# PLWD_MCU_IO.net
KiCad netlist of a schematic drawn in Altium Designer
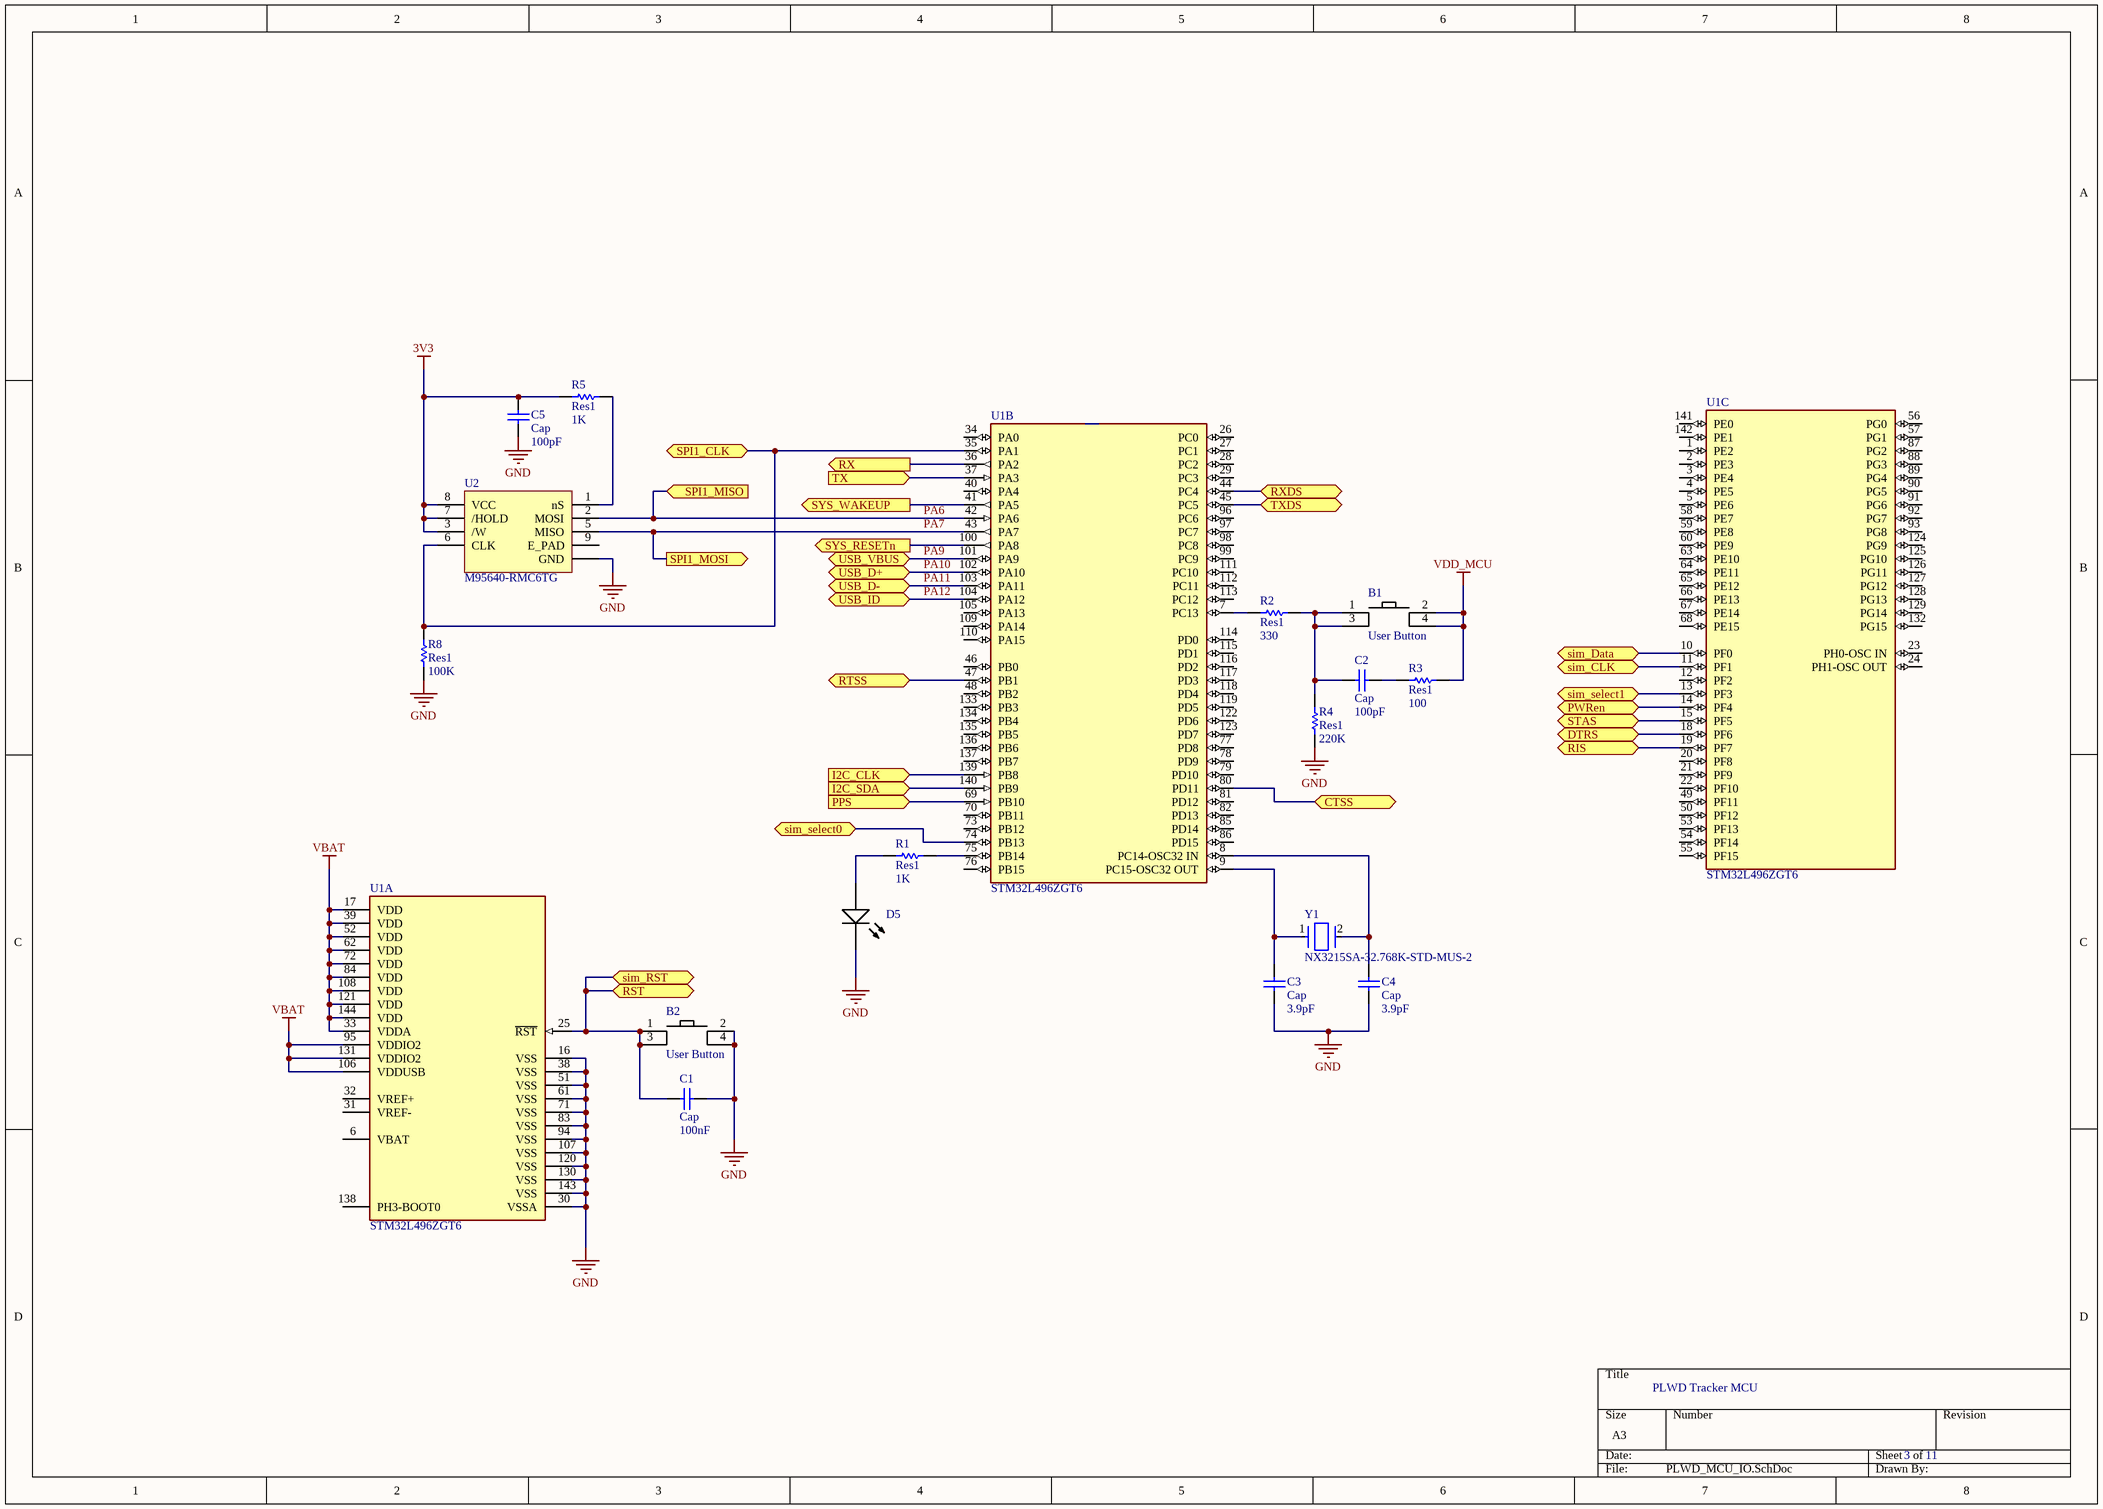
[diagram p0: PLWD_MCU_IO.SchDoc]

(export (version "E")
  (design (tool "Eeschema 10.0.6"))
  (components
    (comp (ref "B1") (value "User Button") (libsource (lib "PLWD_PartLib") (part "button")))
    (comp (ref "B2") (value "User Button") (libsource (lib "PLWD_PartLib") (part "button")))
    (comp (ref "C1")
      (value "Cap")
      (footprint "RAD-0.3")
      (description "Capacitor")
      (fields (field (name "ALTIUM_VALUE") "100nF") (field (name "PUBLISHER") "Altium Limited"))
      (libsource (lib "Miscellaneous Devices") (part "Cap"))
    )
    (comp (ref "C2")
      (value "Cap")
      (footprint "RAD-0.3")
      (description "Capacitor")
      (fields (field (name "ALTIUM_VALUE") "100pF") (field (name "PUBLISHER") "Altium Limited"))
      (libsource (lib "Miscellaneous Devices") (part "Cap"))
    )
    (comp (ref "C3")
      (value "Cap")
      (footprint "RAD-0.3")
      (description "Capacitor")
      (fields (field (name "ALTIUM_VALUE") "3.9pF") (field (name "PUBLISHER") "Altium Limited"))
      (libsource (lib "Miscellaneous Devices") (part "Cap"))
    )
    (comp (ref "C4")
      (value "Cap")
      (footprint "RAD-0.3")
      (description "Capacitor")
      (fields (field (name "ALTIUM_VALUE") "3.9pF") (field (name "PUBLISHER") "Altium Limited"))
      (libsource (lib "Miscellaneous Devices") (part "Cap"))
    )
    (comp (ref "C5")
      (value "Cap")
      (footprint "RAD-0.3")
      (description "Capacitor")
      (fields (field (name "ALTIUM_VALUE") "100pF") (field (name "PUBLISHER") "Altium Limited"))
      (libsource (lib "Miscellaneous Devices") (part "Cap"))
    )
    (comp (ref "D5")
      (value "16-219A/T2D-AR2T1QY/3T")
      (footprint "EVRL-0402-2_V")
      (description "Chip LED, White, 5 V, 10 mA, 30 mW, -40 to 85 degC, 2-Pin SMD (0402), RoHS, Tape and Reel")
      (fields (field (name "POWER") "30mW") (field (name "MANUFACTURER") "Everlight Electronics"))
      (libsource (lib "Carleton University") (part "LED-WHITE-AK-2"))
    )
    (comp (ref "R1")
      (value "Res1")
      (footprint "AXIAL-0.3")
      (description "Resistor")
      (fields (field (name "ALTIUM_VALUE") "1K") (field (name "PUBLISHER") "Altium Limited"))
      (libsource (lib "Miscellaneous Devices") (part "Res1"))
    )
    (comp (ref "R2")
      (value "Res1")
      (footprint "AXIAL-0.3")
      (description "Resistor")
      (fields (field (name "ALTIUM_VALUE") "330") (field (name "PUBLISHER") "Altium Limited"))
      (libsource (lib "Miscellaneous Devices") (part "Res1"))
    )
    (comp (ref "R3")
      (value "Res1")
      (footprint "AXIAL-0.3")
      (description "Resistor")
      (fields (field (name "ALTIUM_VALUE") "100") (field (name "PUBLISHER") "Altium Limited"))
      (libsource (lib "Miscellaneous Devices") (part "Res1"))
    )
    (comp (ref "R4")
      (value "Res1")
      (footprint "AXIAL-0.3")
      (description "Resistor")
      (fields (field (name "ALTIUM_VALUE") "220K") (field (name "PUBLISHER") "Altium Limited"))
      (libsource (lib "Miscellaneous Devices") (part "Res1"))
    )
    (comp (ref "R5")
      (value "Res1")
      (footprint "AXIAL-0.3")
      (description "Resistor")
      (fields (field (name "ALTIUM_VALUE") "1K") (field (name "PUBLISHER") "Altium Limited"))
      (libsource (lib "Miscellaneous Devices") (part "Res1"))
    )
    (comp (ref "R8")
      (value "Res1")
      (footprint "AXIAL-0.3")
      (description "Resistor")
      (fields (field (name "ALTIUM_VALUE") "100K") (field (name "PUBLISHER") "Altium Limited"))
      (libsource (lib "Miscellaneous Devices") (part "Res1"))
    )
    (comp (ref "U1")
      (value "STM32L496ZGT6")
      (footprint "FP-LQFP144-1A-MFG")
      (description "IC MCU 32BIT 1MB FLASH 144LQFP")
      (fields
        (field (name "MANUFACTURER") "STMicroelectronics")
        (field (name "OCTOPART") "https://octopart.com/stm32l496zgt6-stmicroelectronics-80927210")
      )
      (libsource (lib "") (part "f6bd984deb1ec052b3cf6fb0542fb75_2"))
    )
    (comp (ref "U2")
      (value "M95640-RMC6TG")
      (description "M95640 Series 64 Kb (8K x 8) 5.5 V 20 MHz SMT Serial SPI bus EEPROM - UFDFPN-8")
      (fields (field (name "MANUFACTURER") "STMicroelectronics"))
      (libsource (lib "PLWD_PartLib") (part "M95640-RMC6TG"))
    )
    (comp (ref "Y1")
      (value "NX3215SA-32.768K-STD-MUS-2")
      (footprint "FP-NX3215SA-MFG")
      (description "CRYSTAL 32.7680KHZ 12.5PF SMD")
      (libsource (lib "Altium Content Vault") (part "c23a69dc6c9e2f18f2079038eb95dd1"))
    )
  )
  (nets
    (net (code "1") (name "/CTSS") (class "Default")
      (node (ref "U1") (pin "80") (pinfunction "PD11_80") (pintype "bidirectional"))
    )
    (net (code "2") (name "/DTRS") (class "Default")
      (node (ref "U1") (pin "18") (pinfunction "PF6_18") (pintype "bidirectional"))
    )
    (net (code "3") (name "/I2C_CLK") (class "Default")
      (node (ref "U1") (pin "139") (pinfunction "PB8_139") (pintype "input"))
    )
    (net (code "4") (name "/I2C_SDA") (class "Default")
      (node (ref "U1") (pin "140") (pinfunction "PB9_140") (pintype "input"))
    )
    (net (code "5") (name "/PA6") (class "Default")
      (node (ref "U1") (pin "42") (pinfunction "PA6_42") (pintype "input"))
      (node (ref "U2") (pin "2") (pinfunction "MOSI_2") (pintype "passive"))
    )
    (net (code "6") (name "/PA7") (class "Default")
      (node (ref "U1") (pin "43") (pinfunction "PA7_43") (pintype "output"))
      (node (ref "U2") (pin "5") (pinfunction "MISO_5") (pintype "passive"))
    )
    (net (code "7") (name "/PA9") (class "Default")
      (node (ref "U1") (pin "101") (pinfunction "PA9_101") (pintype "bidirectional"))
    )
    (net (code "8") (name "/PA10") (class "Default")
      (node (ref "U1") (pin "102") (pinfunction "PA10_102") (pintype "bidirectional"))
    )
    (net (code "9") (name "/PA11") (class "Default")
      (node (ref "U1") (pin "103") (pinfunction "PA11_103") (pintype "bidirectional"))
    )
    (net (code "10") (name "/PA12") (class "Default")
      (node (ref "U1") (pin "104") (pinfunction "PA12_104") (pintype "bidirectional"))
    )
    (net (code "11") (name "/PPS") (class "Default")
      (node (ref "U1") (pin "69") (pinfunction "PB10_69") (pintype "input"))
    )
    (net (code "12") (name "/PWRen") (class "Default")
      (node (ref "U1") (pin "14") (pinfunction "PF4_14") (pintype "bidirectional"))
    )
    (net (code "13") (name "/RIS") (class "Default")
      (node (ref "U1") (pin "19") (pinfunction "PF7_19") (pintype "bidirectional"))
    )
    (net (code "14") (name "/RST") (class "Default")
      (node (ref "B2") (pin "1") (pintype "passive"))
      (node (ref "B2") (pin "3") (pintype "passive"))
      (node (ref "C1") (pin "1") (pinfunction "1_1") (pintype "passive"))
      (node (ref "U1") (pin "25") (pinfunction "~{RST}_25") (pintype "input"))
    )
    (net (code "15") (name "/RTSS") (class "Default")
      (node (ref "U1") (pin "47") (pinfunction "PB1_47") (pintype "bidirectional"))
    )
    (net (code "16") (name "/RX") (class "Default")
      (node (ref "U1") (pin "36") (pinfunction "PA2_36") (pintype "output"))
    )
    (net (code "17") (name "/RXDS") (class "Default")
      (node (ref "U1") (pin "44") (pinfunction "PC4_44") (pintype "bidirectional"))
    )
    (net (code "18") (name "/SPI1_CLK") (class "Default")
      (node (ref "R8") (pin "2") (pinfunction "2_2") (pintype "passive"))
      (node (ref "U1") (pin "35") (pinfunction "PA1_35") (pintype "bidirectional"))
      (node (ref "U2") (pin "6") (pinfunction "CLK_6") (pintype "passive"))
    )
    (net (code "19") (name "/STAS") (class "Default")
      (node (ref "U1") (pin "15") (pinfunction "PF5_15") (pintype "bidirectional"))
    )
    (net (code "20") (name "/SYS_RESETn") (class "Default")
      (node (ref "U1") (pin "100") (pinfunction "PA8_100") (pintype "output"))
    )
    (net (code "21") (name "/SYS_WAKEUP") (class "Default")
      (node (ref "U1") (pin "41") (pinfunction "PA5_41") (pintype "output"))
    )
    (net (code "22") (name "/TX") (class "Default")
      (node (ref "U1") (pin "37") (pinfunction "PA3_37") (pintype "input"))
    )
    (net (code "23") (name "/TXDS") (class "Default")
      (node (ref "U1") (pin "45") (pinfunction "PC5_45") (pintype "bidirectional"))
    )
    (net (code "24") (name "/sim_CLK") (class "Default")
      (node (ref "U1") (pin "11") (pinfunction "PF1_11") (pintype "bidirectional"))
    )
    (net (code "25") (name "/sim_Data") (class "Default")
      (node (ref "U1") (pin "10") (pinfunction "PF0_10") (pintype "bidirectional"))
    )
    (net (code "26") (name "/sim_select0") (class "Default")
      (node (ref "U1") (pin "74") (pinfunction "PB13_74") (pintype "bidirectional"))
    )
    (net (code "27") (name "/sim_select1") (class "Default")
      (node (ref "U1") (pin "13") (pinfunction "PF3_13") (pintype "bidirectional"))
    )
    (net (code "28") (name "3V3") (class "Default")
      (node (ref "C5") (pin "2") (pinfunction "2_2") (pintype "passive"))
      (node (ref "R5") (pin "1") (pinfunction "1_1") (pintype "passive"))
      (node (ref "U2") (pin "3") (pinfunction "/W_3") (pintype "passive"))
      (node (ref "U2") (pin "7") (pinfunction "/HOLD_7") (pintype "passive"))
      (node (ref "U2") (pin "8") (pinfunction "VCC_8") (pintype "passive"))
    )
    (net (code "29") (name "GND") (class "Default")
      (node (ref "B2") (pin "2") (pintype "passive"))
      (node (ref "B2") (pin "4") (pintype "passive"))
      (node (ref "C1") (pin "2") (pinfunction "2_2") (pintype "passive"))
      (node (ref "C3") (pin "1") (pinfunction "1_1") (pintype "passive"))
      (node (ref "C4") (pin "1") (pinfunction "1_1") (pintype "passive"))
      (node (ref "C5") (pin "1") (pinfunction "1_1") (pintype "passive"))
      (node (ref "D5") (pin "2") (pinfunction "K_2") (pintype "passive"))
      (node (ref "R4") (pin "1") (pinfunction "1_1") (pintype "passive"))
      (node (ref "R8") (pin "1") (pinfunction "1_1") (pintype "passive"))
      (node (ref "U1") (pin "107") (pinfunction "VSS_107") (pintype "power_in"))
      (node (ref "U1") (pin "120") (pinfunction "VSS_120") (pintype "power_in"))
      (node (ref "U1") (pin "130") (pinfunction "VSS_130") (pintype "power_in"))
      (node (ref "U1") (pin "143") (pinfunction "VSS_143") (pintype "power_in"))
      (node (ref "U1") (pin "16") (pinfunction "VSS_16") (pintype "power_in"))
      (node (ref "U1") (pin "30") (pinfunction "VSSA_30") (pintype "power_in"))
      (node (ref "U1") (pin "38") (pinfunction "VSS_38") (pintype "power_in"))
      (node (ref "U1") (pin "51") (pinfunction "VSS_51") (pintype "power_in"))
      (node (ref "U1") (pin "61") (pinfunction "VSS_61") (pintype "power_in"))
      (node (ref "U1") (pin "71") (pinfunction "VSS_71") (pintype "power_in"))
      (node (ref "U1") (pin "83") (pinfunction "VSS_83") (pintype "power_in"))
      (node (ref "U1") (pin "94") (pinfunction "VSS_94") (pintype "power_in"))
      (node (ref "U2") (pin "4") (pinfunction "GND_4") (pintype "passive"))
    )
    (net (code "30") (name "Net-(B1-Pad1)") (class "Default")
      (node (ref "B1") (pin "1") (pintype "passive"))
      (node (ref "B1") (pin "3") (pintype "passive"))
      (node (ref "C2") (pin "1") (pinfunction "1_1") (pintype "passive"))
      (node (ref "R2") (pin "2") (pinfunction "2_2") (pintype "passive"))
      (node (ref "R4") (pin "2") (pinfunction "2_2") (pintype "passive"))
    )
    (net (code "31") (name "Net-(C2-Pad2)") (class "Default")
      (node (ref "C2") (pin "2") (pinfunction "2_2") (pintype "passive"))
      (node (ref "R3") (pin "1") (pinfunction "1_1") (pintype "passive"))
    )
    (net (code "32") (name "Net-(D5-A)") (class "Default")
      (node (ref "D5") (pin "1") (pinfunction "A_1") (pintype "passive"))
      (node (ref "R1") (pin "1") (pinfunction "1_1") (pintype "passive"))
    )
    (net (code "33") (name "Net-(U1B-PB14)") (class "Default")
      (node (ref "R1") (pin "2") (pinfunction "2_2") (pintype "passive"))
      (node (ref "U1") (pin "75") (pinfunction "PB14_75") (pintype "bidirectional"))
    )
    (net (code "34") (name "Net-(U1B-PC13)") (class "Default")
      (node (ref "R2") (pin "1") (pinfunction "1_1") (pintype "passive"))
      (node (ref "U1") (pin "7") (pinfunction "PC13_7") (pintype "bidirectional"))
    )
    (net (code "35") (name "Net-(U1B-PC14-OSC32_IN)") (class "Default")
      (node (ref "C4") (pin "2") (pinfunction "2_2") (pintype "passive"))
      (node (ref "U1") (pin "8") (pinfunction "PC14-OSC32_IN_8") (pintype "bidirectional"))
      (node (ref "Y1") (pin "2") (pinfunction "2_2") (pintype "passive"))
    )
    (net (code "36") (name "Net-(U1B-PC15-OSC32_OUT)") (class "Default")
      (node (ref "C3") (pin "2") (pinfunction "2_2") (pintype "passive"))
      (node (ref "U1") (pin "9") (pinfunction "PC15-OSC32_OUT_9") (pintype "bidirectional"))
      (node (ref "Y1") (pin "1") (pinfunction "1_1") (pintype "passive"))
    )
    (net (code "37") (name "Net-(U2-nS)") (class "Default")
      (node (ref "R5") (pin "2") (pinfunction "2_2") (pintype "passive"))
      (node (ref "U2") (pin "1") (pinfunction "nS_1") (pintype "passive"))
    )
    (net (code "38") (name "VBAT") (class "Default")
      (node (ref "U1") (pin "106") (pinfunction "VDDUSB_106") (pintype "power_in"))
      (node (ref "U1") (pin "108") (pinfunction "VDD_108") (pintype "power_in"))
      (node (ref "U1") (pin "121") (pinfunction "VDD_121") (pintype "power_in"))
      (node (ref "U1") (pin "131") (pinfunction "VDDIO2_131") (pintype "power_in"))
      (node (ref "U1") (pin "144") (pinfunction "VDD_144") (pintype "power_in"))
      (node (ref "U1") (pin "17") (pinfunction "VDD_17") (pintype "power_in"))
      (node (ref "U1") (pin "33") (pinfunction "VDDA_33") (pintype "power_in"))
      (node (ref "U1") (pin "39") (pinfunction "VDD_39") (pintype "power_in"))
      (node (ref "U1") (pin "52") (pinfunction "VDD_52") (pintype "power_in"))
      (node (ref "U1") (pin "62") (pinfunction "VDD_62") (pintype "power_in"))
      (node (ref "U1") (pin "72") (pinfunction "VDD_72") (pintype "power_in"))
      (node (ref "U1") (pin "84") (pinfunction "VDD_84") (pintype "power_in"))
      (node (ref "U1") (pin "95") (pinfunction "VDDIO2_95") (pintype "power_in"))
    )
    (net (code "39") (name "VDD_MCU") (class "Default")
      (node (ref "B1") (pin "2") (pintype "passive"))
      (node (ref "B1") (pin "4") (pintype "passive"))
      (node (ref "R3") (pin "2") (pinfunction "2_2") (pintype "passive"))
    )
    (net (code "40") (name "unconnected-(U1A-PH3-BOOT0-Pad138)") (class "Default")
      (node (ref "U1") (pin "138") (pinfunction "PH3-BOOT0_138") (pintype "passive"))
    )
    (net (code "41") (name "unconnected-(U1A-VBAT-Pad6)") (class "Default")
      (node (ref "U1") (pin "6") (pinfunction "VBAT_6") (pintype "power_in"))
    )
    (net (code "42") (name "unconnected-(U1A-VREF+-Pad32)") (class "Default")
      (node (ref "U1") (pin "32") (pinfunction "VREF+_32") (pintype "power_in"))
    )
    (net (code "43") (name "unconnected-(U1A-VREF--Pad31)") (class "Default")
      (node (ref "U1") (pin "31") (pinfunction "VREF-_31") (pintype "power_in"))
    )
    (net (code "44") (name "unconnected-(U1B-PA0-Pad34)") (class "Default")
      (node (ref "U1") (pin "34") (pinfunction "PA0_34") (pintype "bidirectional"))
    )
    (net (code "45") (name "unconnected-(U1B-PA4-Pad40)") (class "Default")
      (node (ref "U1") (pin "40") (pinfunction "PA4_40") (pintype "bidirectional"))
    )
    (net (code "46") (name "unconnected-(U1B-PA13-Pad105)") (class "Default")
      (node (ref "U1") (pin "105") (pinfunction "PA13_105") (pintype "bidirectional"))
    )
    (net (code "47") (name "unconnected-(U1B-PA14-Pad109)") (class "Default")
      (node (ref "U1") (pin "109") (pinfunction "PA14_109") (pintype "bidirectional"))
    )
    (net (code "48") (name "unconnected-(U1B-PA15-Pad110)") (class "Default")
      (node (ref "U1") (pin "110") (pinfunction "PA15_110") (pintype "bidirectional"))
    )
    (net (code "49") (name "unconnected-(U1B-PB0-Pad46)") (class "Default")
      (node (ref "U1") (pin "46") (pinfunction "PB0_46") (pintype "bidirectional"))
    )
    (net (code "50") (name "unconnected-(U1B-PB2-Pad48)") (class "Default")
      (node (ref "U1") (pin "48") (pinfunction "PB2_48") (pintype "bidirectional"))
    )
    (net (code "51") (name "unconnected-(U1B-PB3-Pad133)") (class "Default")
      (node (ref "U1") (pin "133") (pinfunction "PB3_133") (pintype "bidirectional"))
    )
    (net (code "52") (name "unconnected-(U1B-PB4-Pad134)") (class "Default")
      (node (ref "U1") (pin "134") (pinfunction "PB4_134") (pintype "bidirectional"))
    )
    (net (code "53") (name "unconnected-(U1B-PB5-Pad135)") (class "Default")
      (node (ref "U1") (pin "135") (pinfunction "PB5_135") (pintype "bidirectional"))
    )
    (net (code "54") (name "unconnected-(U1B-PB6-Pad136)") (class "Default")
      (node (ref "U1") (pin "136") (pinfunction "PB6_136") (pintype "bidirectional"))
    )
    (net (code "55") (name "unconnected-(U1B-PB7-Pad137)") (class "Default")
      (node (ref "U1") (pin "137") (pinfunction "PB7_137") (pintype "bidirectional"))
    )
    (net (code "56") (name "unconnected-(U1B-PB11-Pad70)") (class "Default")
      (node (ref "U1") (pin "70") (pinfunction "PB11_70") (pintype "bidirectional"))
    )
    (net (code "57") (name "unconnected-(U1B-PB12-Pad73)") (class "Default")
      (node (ref "U1") (pin "73") (pinfunction "PB12_73") (pintype "bidirectional"))
    )
    (net (code "58") (name "unconnected-(U1B-PB15-Pad76)") (class "Default")
      (node (ref "U1") (pin "76") (pinfunction "PB15_76") (pintype "bidirectional"))
    )
    (net (code "59") (name "unconnected-(U1B-PC0-Pad26)") (class "Default")
      (node (ref "U1") (pin "26") (pinfunction "PC0_26") (pintype "bidirectional"))
    )
    (net (code "60") (name "unconnected-(U1B-PC1-Pad27)") (class "Default")
      (node (ref "U1") (pin "27") (pinfunction "PC1_27") (pintype "bidirectional"))
    )
    (net (code "61") (name "unconnected-(U1B-PC2-Pad28)") (class "Default")
      (node (ref "U1") (pin "28") (pinfunction "PC2_28") (pintype "bidirectional"))
    )
    (net (code "62") (name "unconnected-(U1B-PC3-Pad29)") (class "Default")
      (node (ref "U1") (pin "29") (pinfunction "PC3_29") (pintype "bidirectional"))
    )
    (net (code "63") (name "unconnected-(U1B-PC6-Pad96)") (class "Default")
      (node (ref "U1") (pin "96") (pinfunction "PC6_96") (pintype "bidirectional"))
    )
    (net (code "64") (name "unconnected-(U1B-PC7-Pad97)") (class "Default")
      (node (ref "U1") (pin "97") (pinfunction "PC7_97") (pintype "bidirectional"))
    )
    (net (code "65") (name "unconnected-(U1B-PC8-Pad98)") (class "Default")
      (node (ref "U1") (pin "98") (pinfunction "PC8_98") (pintype "bidirectional"))
    )
    (net (code "66") (name "unconnected-(U1B-PC9-Pad99)") (class "Default")
      (node (ref "U1") (pin "99") (pinfunction "PC9_99") (pintype "bidirectional"))
    )
    (net (code "67") (name "unconnected-(U1B-PC10-Pad111)") (class "Default")
      (node (ref "U1") (pin "111") (pinfunction "PC10_111") (pintype "bidirectional"))
    )
    (net (code "68") (name "unconnected-(U1B-PC11-Pad112)") (class "Default")
      (node (ref "U1") (pin "112") (pinfunction "PC11_112") (pintype "bidirectional"))
    )
    (net (code "69") (name "unconnected-(U1B-PC12-Pad113)") (class "Default")
      (node (ref "U1") (pin "113") (pinfunction "PC12_113") (pintype "bidirectional"))
    )
    (net (code "70") (name "unconnected-(U1B-PD0-Pad114)") (class "Default")
      (node (ref "U1") (pin "114") (pinfunction "PD0_114") (pintype "bidirectional"))
    )
    (net (code "71") (name "unconnected-(U1B-PD1-Pad115)") (class "Default")
      (node (ref "U1") (pin "115") (pinfunction "PD1_115") (pintype "bidirectional"))
    )
    (net (code "72") (name "unconnected-(U1B-PD2-Pad116)") (class "Default")
      (node (ref "U1") (pin "116") (pinfunction "PD2_116") (pintype "bidirectional"))
    )
    (net (code "73") (name "unconnected-(U1B-PD3-Pad117)") (class "Default")
      (node (ref "U1") (pin "117") (pinfunction "PD3_117") (pintype "bidirectional"))
    )
    (net (code "74") (name "unconnected-(U1B-PD4-Pad118)") (class "Default")
      (node (ref "U1") (pin "118") (pinfunction "PD4_118") (pintype "bidirectional"))
    )
    (net (code "75") (name "unconnected-(U1B-PD5-Pad119)") (class "Default")
      (node (ref "U1") (pin "119") (pinfunction "PD5_119") (pintype "bidirectional"))
    )
    (net (code "76") (name "unconnected-(U1B-PD6-Pad122)") (class "Default")
      (node (ref "U1") (pin "122") (pinfunction "PD6_122") (pintype "bidirectional"))
    )
    (net (code "77") (name "unconnected-(U1B-PD7-Pad123)") (class "Default")
      (node (ref "U1") (pin "123") (pinfunction "PD7_123") (pintype "bidirectional"))
    )
    (net (code "78") (name "unconnected-(U1B-PD8-Pad77)") (class "Default")
      (node (ref "U1") (pin "77") (pinfunction "PD8_77") (pintype "bidirectional"))
    )
    (net (code "79") (name "unconnected-(U1B-PD9-Pad78)") (class "Default")
      (node (ref "U1") (pin "78") (pinfunction "PD9_78") (pintype "bidirectional"))
    )
    (net (code "80") (name "unconnected-(U1B-PD10-Pad79)") (class "Default")
      (node (ref "U1") (pin "79") (pinfunction "PD10_79") (pintype "bidirectional"))
    )
    (net (code "81") (name "unconnected-(U1B-PD12-Pad81)") (class "Default")
      (node (ref "U1") (pin "81") (pinfunction "PD12_81") (pintype "bidirectional"))
    )
    (net (code "82") (name "unconnected-(U1B-PD13-Pad82)") (class "Default")
      (node (ref "U1") (pin "82") (pinfunction "PD13_82") (pintype "bidirectional"))
    )
    (net (code "83") (name "unconnected-(U1B-PD14-Pad85)") (class "Default")
      (node (ref "U1") (pin "85") (pinfunction "PD14_85") (pintype "bidirectional"))
    )
    (net (code "84") (name "unconnected-(U1B-PD15-Pad86)") (class "Default")
      (node (ref "U1") (pin "86") (pinfunction "PD15_86") (pintype "bidirectional"))
    )
    (net (code "85") (name "unconnected-(U1C-PE0-Pad141)") (class "Default")
      (node (ref "U1") (pin "141") (pinfunction "PE0_141") (pintype "bidirectional"))
    )
    (net (code "86") (name "unconnected-(U1C-PE1-Pad142)") (class "Default")
      (node (ref "U1") (pin "142") (pinfunction "PE1_142") (pintype "bidirectional"))
    )
    (net (code "87") (name "unconnected-(U1C-PE2-Pad1)") (class "Default")
      (node (ref "U1") (pin "1") (pinfunction "PE2_1") (pintype "bidirectional"))
    )
    (net (code "88") (name "unconnected-(U1C-PE3-Pad2)") (class "Default")
      (node (ref "U1") (pin "2") (pinfunction "PE3_2") (pintype "bidirectional"))
    )
    (net (code "89") (name "unconnected-(U1C-PE4-Pad3)") (class "Default")
      (node (ref "U1") (pin "3") (pinfunction "PE4_3") (pintype "bidirectional"))
    )
    (net (code "90") (name "unconnected-(U1C-PE5-Pad4)") (class "Default")
      (node (ref "U1") (pin "4") (pinfunction "PE5_4") (pintype "bidirectional"))
    )
    (net (code "91") (name "unconnected-(U1C-PE6-Pad5)") (class "Default")
      (node (ref "U1") (pin "5") (pinfunction "PE6_5") (pintype "bidirectional"))
    )
    (net (code "92") (name "unconnected-(U1C-PE7-Pad58)") (class "Default")
      (node (ref "U1") (pin "58") (pinfunction "PE7_58") (pintype "bidirectional"))
    )
    (net (code "93") (name "unconnected-(U1C-PE8-Pad59)") (class "Default")
      (node (ref "U1") (pin "59") (pinfunction "PE8_59") (pintype "bidirectional"))
    )
    (net (code "94") (name "unconnected-(U1C-PE9-Pad60)") (class "Default")
      (node (ref "U1") (pin "60") (pinfunction "PE9_60") (pintype "bidirectional"))
    )
    (net (code "95") (name "unconnected-(U1C-PE10-Pad63)") (class "Default")
      (node (ref "U1") (pin "63") (pinfunction "PE10_63") (pintype "bidirectional"))
    )
    (net (code "96") (name "unconnected-(U1C-PE11-Pad64)") (class "Default")
      (node (ref "U1") (pin "64") (pinfunction "PE11_64") (pintype "bidirectional"))
    )
    (net (code "97") (name "unconnected-(U1C-PE12-Pad65)") (class "Default")
      (node (ref "U1") (pin "65") (pinfunction "PE12_65") (pintype "bidirectional"))
    )
    (net (code "98") (name "unconnected-(U1C-PE13-Pad66)") (class "Default")
      (node (ref "U1") (pin "66") (pinfunction "PE13_66") (pintype "bidirectional"))
    )
    (net (code "99") (name "unconnected-(U1C-PE14-Pad67)") (class "Default")
      (node (ref "U1") (pin "67") (pinfunction "PE14_67") (pintype "bidirectional"))
    )
    (net (code "100") (name "unconnected-(U1C-PE15-Pad68)") (class "Default")
      (node (ref "U1") (pin "68") (pinfunction "PE15_68") (pintype "bidirectional"))
    )
    (net (code "101") (name "unconnected-(U1C-PF2-Pad12)") (class "Default")
      (node (ref "U1") (pin "12") (pinfunction "PF2_12") (pintype "bidirectional"))
    )
    (net (code "102") (name "unconnected-(U1C-PF8-Pad20)") (class "Default")
      (node (ref "U1") (pin "20") (pinfunction "PF8_20") (pintype "bidirectional"))
    )
    (net (code "103") (name "unconnected-(U1C-PF9-Pad21)") (class "Default")
      (node (ref "U1") (pin "21") (pinfunction "PF9_21") (pintype "bidirectional"))
    )
    (net (code "104") (name "unconnected-(U1C-PF10-Pad22)") (class "Default")
      (node (ref "U1") (pin "22") (pinfunction "PF10_22") (pintype "bidirectional"))
    )
    (net (code "105") (name "unconnected-(U1C-PF11-Pad49)") (class "Default")
      (node (ref "U1") (pin "49") (pinfunction "PF11_49") (pintype "bidirectional"))
    )
    (net (code "106") (name "unconnected-(U1C-PF12-Pad50)") (class "Default")
      (node (ref "U1") (pin "50") (pinfunction "PF12_50") (pintype "bidirectional"))
    )
    (net (code "107") (name "unconnected-(U1C-PF13-Pad53)") (class "Default")
      (node (ref "U1") (pin "53") (pinfunction "PF13_53") (pintype "bidirectional"))
    )
    (net (code "108") (name "unconnected-(U1C-PF14-Pad54)") (class "Default")
      (node (ref "U1") (pin "54") (pinfunction "PF14_54") (pintype "bidirectional"))
    )
    (net (code "109") (name "unconnected-(U1C-PF15-Pad55)") (class "Default")
      (node (ref "U1") (pin "55") (pinfunction "PF15_55") (pintype "bidirectional"))
    )
    (net (code "110") (name "unconnected-(U1C-PG0-Pad56)") (class "Default")
      (node (ref "U1") (pin "56") (pinfunction "PG0_56") (pintype "bidirectional"))
    )
    (net (code "111") (name "unconnected-(U1C-PG1-Pad57)") (class "Default")
      (node (ref "U1") (pin "57") (pinfunction "PG1_57") (pintype "bidirectional"))
    )
    (net (code "112") (name "unconnected-(U1C-PG2-Pad87)") (class "Default")
      (node (ref "U1") (pin "87") (pinfunction "PG2_87") (pintype "bidirectional"))
    )
    (net (code "113") (name "unconnected-(U1C-PG3-Pad88)") (class "Default")
      (node (ref "U1") (pin "88") (pinfunction "PG3_88") (pintype "bidirectional"))
    )
    (net (code "114") (name "unconnected-(U1C-PG4-Pad89)") (class "Default")
      (node (ref "U1") (pin "89") (pinfunction "PG4_89") (pintype "bidirectional"))
    )
    (net (code "115") (name "unconnected-(U1C-PG5-Pad90)") (class "Default")
      (node (ref "U1") (pin "90") (pinfunction "PG5_90") (pintype "bidirectional"))
    )
    (net (code "116") (name "unconnected-(U1C-PG6-Pad91)") (class "Default")
      (node (ref "U1") (pin "91") (pinfunction "PG6_91") (pintype "bidirectional"))
    )
    (net (code "117") (name "unconnected-(U1C-PG7-Pad92)") (class "Default")
      (node (ref "U1") (pin "92") (pinfunction "PG7_92") (pintype "bidirectional"))
    )
    (net (code "118") (name "unconnected-(U1C-PG8-Pad93)") (class "Default")
      (node (ref "U1") (pin "93") (pinfunction "PG8_93") (pintype "bidirectional"))
    )
    (net (code "119") (name "unconnected-(U1C-PG9-Pad124)") (class "Default")
      (node (ref "U1") (pin "124") (pinfunction "PG9_124") (pintype "bidirectional"))
    )
    (net (code "120") (name "unconnected-(U1C-PG10-Pad125)") (class "Default")
      (node (ref "U1") (pin "125") (pinfunction "PG10_125") (pintype "bidirectional"))
    )
    (net (code "121") (name "unconnected-(U1C-PG11-Pad126)") (class "Default")
      (node (ref "U1") (pin "126") (pinfunction "PG11_126") (pintype "bidirectional"))
    )
    (net (code "122") (name "unconnected-(U1C-PG12-Pad127)") (class "Default")
      (node (ref "U1") (pin "127") (pinfunction "PG12_127") (pintype "bidirectional"))
    )
    (net (code "123") (name "unconnected-(U1C-PG13-Pad128)") (class "Default")
      (node (ref "U1") (pin "128") (pinfunction "PG13_128") (pintype "bidirectional"))
    )
    (net (code "124") (name "unconnected-(U1C-PG14-Pad129)") (class "Default")
      (node (ref "U1") (pin "129") (pinfunction "PG14_129") (pintype "bidirectional"))
    )
    (net (code "125") (name "unconnected-(U1C-PG15-Pad132)") (class "Default")
      (node (ref "U1") (pin "132") (pinfunction "PG15_132") (pintype "bidirectional"))
    )
    (net (code "126") (name "unconnected-(U1C-PH0-OSC_IN-Pad23)") (class "Default")
      (node (ref "U1") (pin "23") (pinfunction "PH0-OSC_IN_23") (pintype "bidirectional"))
    )
    (net (code "127") (name "unconnected-(U1C-PH1-OSC_OUT-Pad24)") (class "Default")
      (node (ref "U1") (pin "24") (pinfunction "PH1-OSC_OUT_24") (pintype "bidirectional"))
    )
    (net (code "128") (name "unconnected-(U2-E_PAD-Pad9)") (class "Default")
      (node (ref "U2") (pin "9") (pinfunction "E_PAD_9") (pintype "passive"))
    )
  )
)
